# EmergencyStop_-_Rev_A3.net
KiCad netlist of a schematic drawn in EAGLE
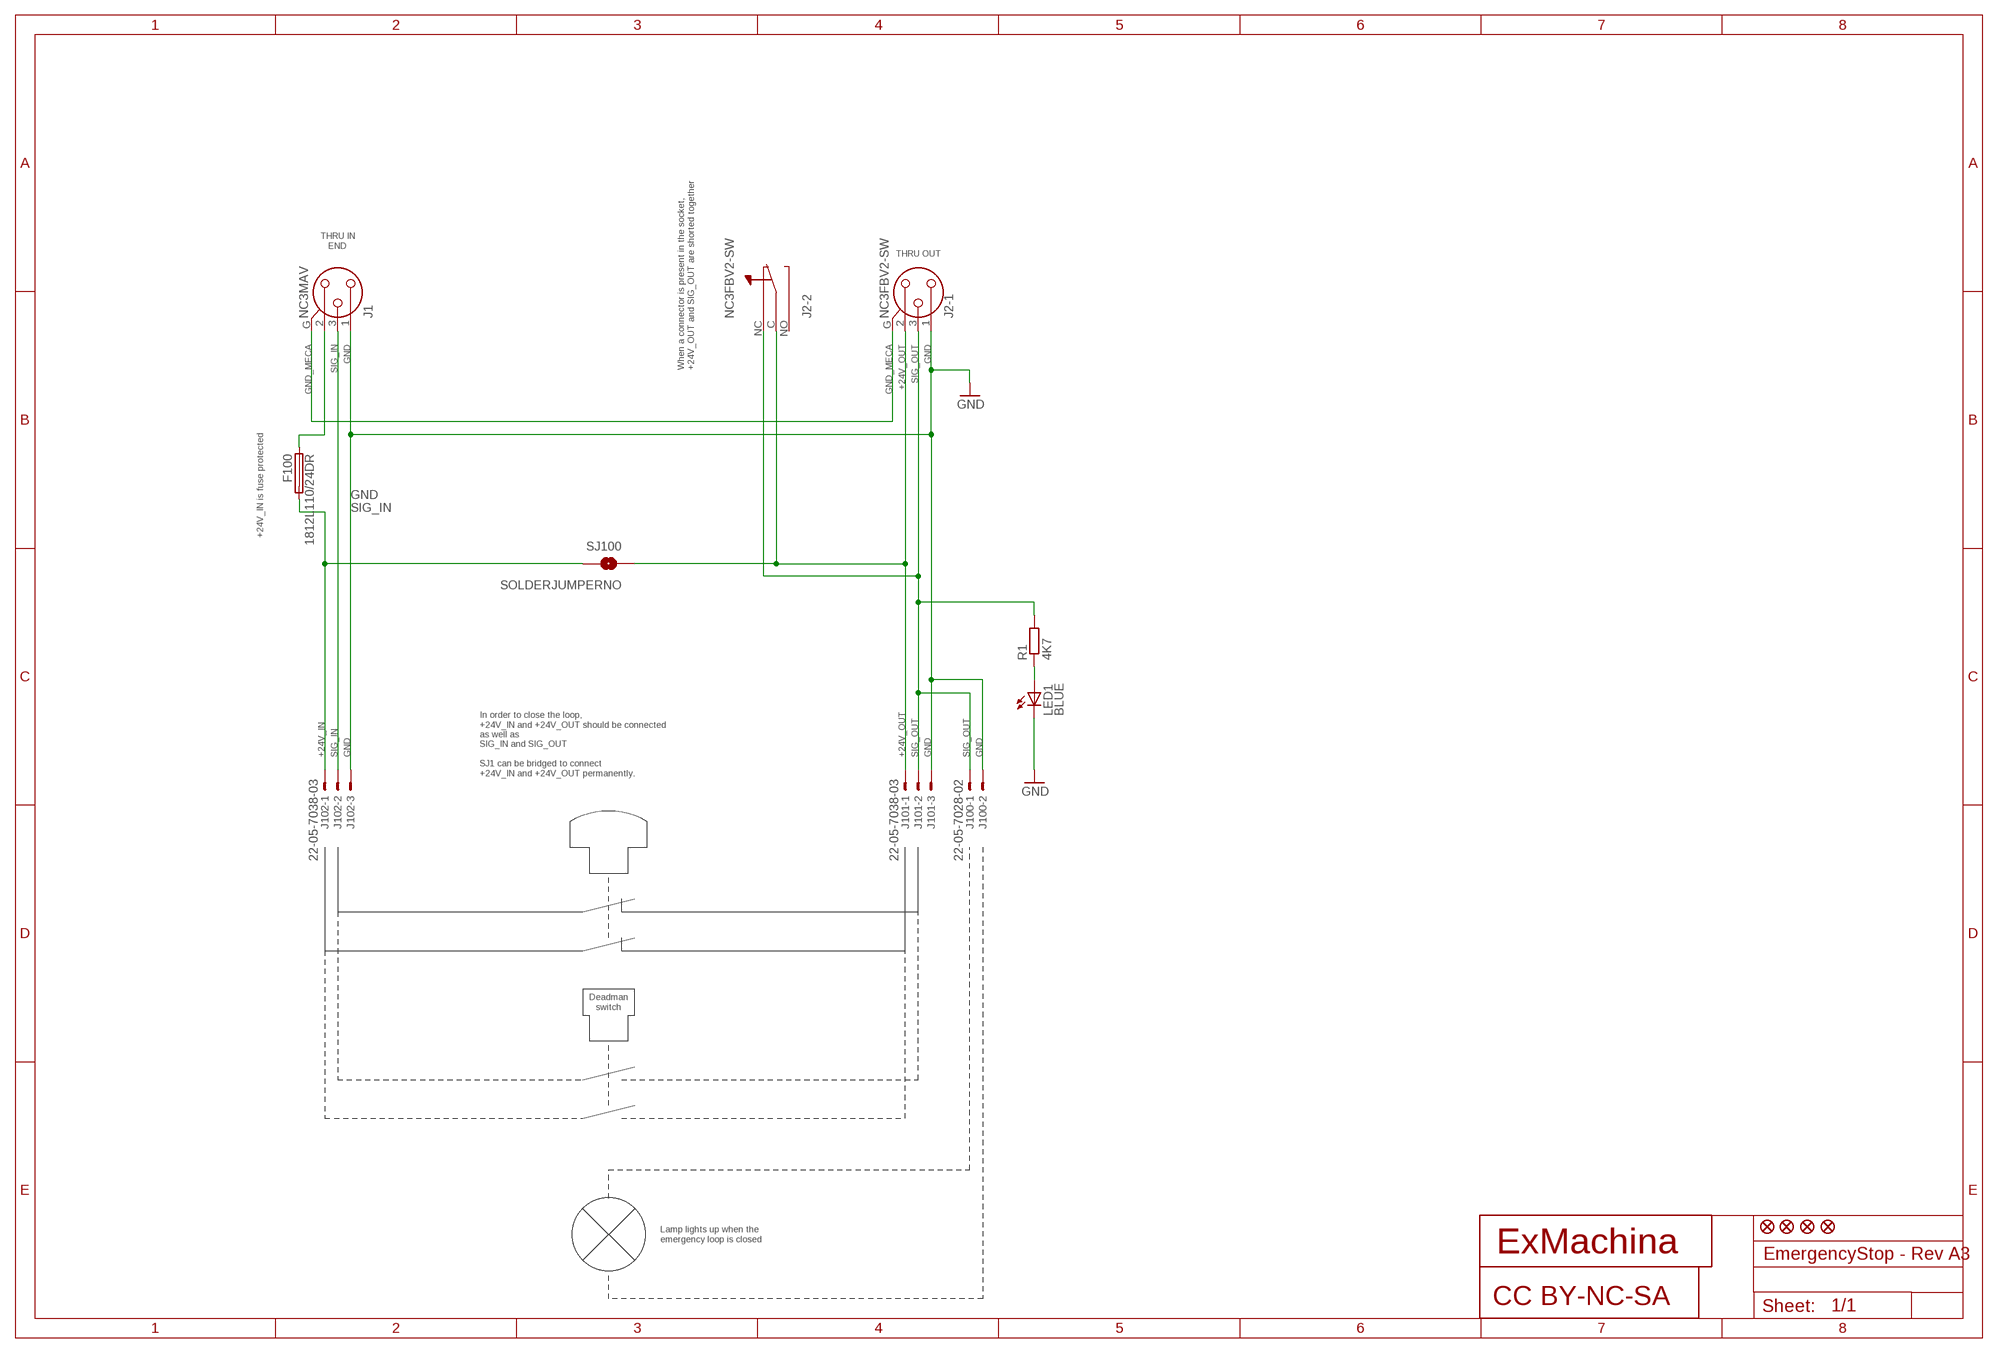
[diagram p0: schematic, sheet 1]

(export (version "E")
  (design (tool "Eeschema 10.0.6"))
  (components
    (comp (ref "CC100")
      (value "CC-BY-NC-SA")
      (footprint "eagle-import:CC-BY-NC-SA")
      (libsource (lib "eagle-import") (part "CC-BY-NC-SA"))
    )
    (comp (ref "F100")
      (value "1812L110/24DR")
      (footprint "eagle-import:LITTLEFUSE_SMD")
      (libsource (lib "eagle-import") (part "1812L110/24DR"))
    )
    (comp (ref "J1")
      (value "NC3MAV")
      (footprint "eagle-import:NC3MAV")
      (fields (field (name "MF") "FARNELL") (field (name "OC_NEWARK") "unknown"))
      (libsource (lib "eagle-import") (part "NC3MAV"))
    )
    (comp (ref "J2")
      (value "NC3FBV2-SW")
      (footprint "eagle-import:NC3FBV2-SW")
      (fields (field (name "OC_NEWARK") "unknown"))
      (libsource (lib "eagle-import") (part "NC3?-SWFBV2"))
    )
    (comp (ref "J100")
      (value "22-05-7028-02")
      (footprint "eagle-import:7395-02")
      (libsource (lib "eagle-import") (part "22-?-0205-7028"))
    )
    (comp (ref "J101")
      (value "22-05-7038-03")
      (footprint "eagle-import:7395-03")
      (libsource (lib "eagle-import") (part "22-?-0305-7038"))
    )
    (comp (ref "J102")
      (value "22-05-7038-03")
      (footprint "eagle-import:7395-03")
      (libsource (lib "eagle-import") (part "22-?-0305-7038"))
    )
    (comp (ref "JP100")
      (value "FIDUCIAL1X2")
      (footprint "eagle-import:FIDUCIAL-1X2")
      (libsource (lib "eagle-import") (part "FIDUCIAL1X2"))
    )
    (comp (ref "JP101")
      (value "FIDUCIAL1X2")
      (footprint "eagle-import:FIDUCIAL-1X2")
      (libsource (lib "eagle-import") (part "FIDUCIAL1X2"))
    )
    (comp (ref "JP102")
      (value "FIDUCIAL1X2")
      (footprint "eagle-import:FIDUCIAL-1X2")
      (libsource (lib "eagle-import") (part "FIDUCIAL1X2"))
    )
    (comp (ref "JP103")
      (value "FIDUCIAL1X2")
      (footprint "eagle-import:FIDUCIAL-1X2")
      (libsource (lib "eagle-import") (part "FIDUCIAL1X2"))
    )
    (comp (ref "LED1")
      (value "BLUE")
      (footprint "eagle-import:CHIPLED_0603")
      (fields (field (name "MPN") "OVS-0603"))
      (libsource (lib "eagle-import") (part "LEDCHIPLED_0603"))
    )
    (comp (ref "R1")
      (value "4K7")
      (footprint "eagle-import:R0603")
      (fields (field (name "MPN") "RC0603FR-074K7L"))
      (libsource (lib "eagle-import") (part "R-EU_R0603"))
    )
    (comp (ref "SJ100")
      (value "SOLDERJUMPERNO")
      (footprint "eagle-import:SJ_2S-NO")
      (libsource (lib "eagle-import") (part "SOLDERJUMPERNO"))
    )
    (comp (ref "T100")
      (value "EXMACHINA-LOGO-NAME")
      (footprint "eagle-import:EXM-LOGO-BASELINE")
      (libsource (lib "eagle-import") (part "EXMACHINA-LOGO-NAME"))
    )
  )
  (nets
    (net (code "1") (name "/+24V_IN") (class "Default")
      (node (ref "F100") (pin "2") (pinfunction "2_2") (pintype "passive"))
      (node (ref "J102") (pin "1") (pinfunction "S_1") (pintype "passive"))
      (node (ref "SJ100") (pin "2") (pinfunction "2_2") (pintype "passive"))
    )
    (net (code "2") (name "/+24V_OUT") (class "Default")
      (node (ref "J101") (pin "1") (pinfunction "S_1") (pintype "passive"))
      (node (ref "J2") (pin "2") (pinfunction "2_2") (pintype "passive"))
      (node (ref "J2") (pin "C") (pinfunction "N_C") (pintype "passive"))
      (node (ref "SJ100") (pin "1") (pinfunction "1_1") (pintype "passive"))
    )
    (net (code "3") (name "/GND_MECA") (class "Default")
      (node (ref "J1") (pin "G") (pinfunction "G_G") (pintype "passive"))
      (node (ref "J2") (pin "G") (pinfunction "G_G") (pintype "passive"))
    )
    (net (code "4") (name "/SIG_IN") (class "Default")
      (node (ref "J1") (pin "3") (pinfunction "3_3") (pintype "passive"))
      (node (ref "J102") (pin "2") (pinfunction "S_2") (pintype "passive"))
    )
    (net (code "5") (name "/SIG_OUT") (class "Default")
      (node (ref "J100") (pin "1") (pinfunction "S_1") (pintype "passive"))
      (node (ref "J101") (pin "2") (pinfunction "S_2") (pintype "passive"))
      (node (ref "J2") (pin "3") (pinfunction "3_3") (pintype "passive"))
      (node (ref "J2") (pin "NC") (pinfunction "NC_NC") (pintype "passive"))
      (node (ref "R1") (pin "2") (pinfunction "2_2") (pintype "passive"))
    )
    (net (code "6") (name "GND") (class "Default")
      (node (ref "J1") (pin "1") (pinfunction "1_1") (pintype "passive"))
      (node (ref "J100") (pin "2") (pinfunction "S_2") (pintype "passive"))
      (node (ref "J101") (pin "3") (pinfunction "S_3") (pintype "passive"))
      (node (ref "J102") (pin "3") (pinfunction "S_3") (pintype "passive"))
      (node (ref "J2") (pin "1") (pinfunction "1_1") (pintype "passive"))
      (node (ref "LED1") (pin "C") (pinfunction "C_C") (pintype "passive"))
    )
    (net (code "7") (name "Net-(F100-Pad1)") (class "Default")
      (node (ref "F100") (pin "1") (pinfunction "1_1") (pintype "passive"))
      (node (ref "J1") (pin "2") (pinfunction "2_2") (pintype "passive"))
    )
    (net (code "8") (name "Net-(LED1-PadA)") (class "Default")
      (node (ref "LED1") (pin "A") (pinfunction "A_A") (pintype "passive"))
      (node (ref "R1") (pin "1") (pinfunction "1_1") (pintype "passive"))
    )
    (net (code "9") (name "unconnected-(J2-PadNO)") (class "Default")
      (node (ref "J2") (pin "NO") (pinfunction "NO_NO") (pintype "passive"))
    )
  )
)
